# FPGA.net
KiCad netlist of a schematic drawn in Altium Designer
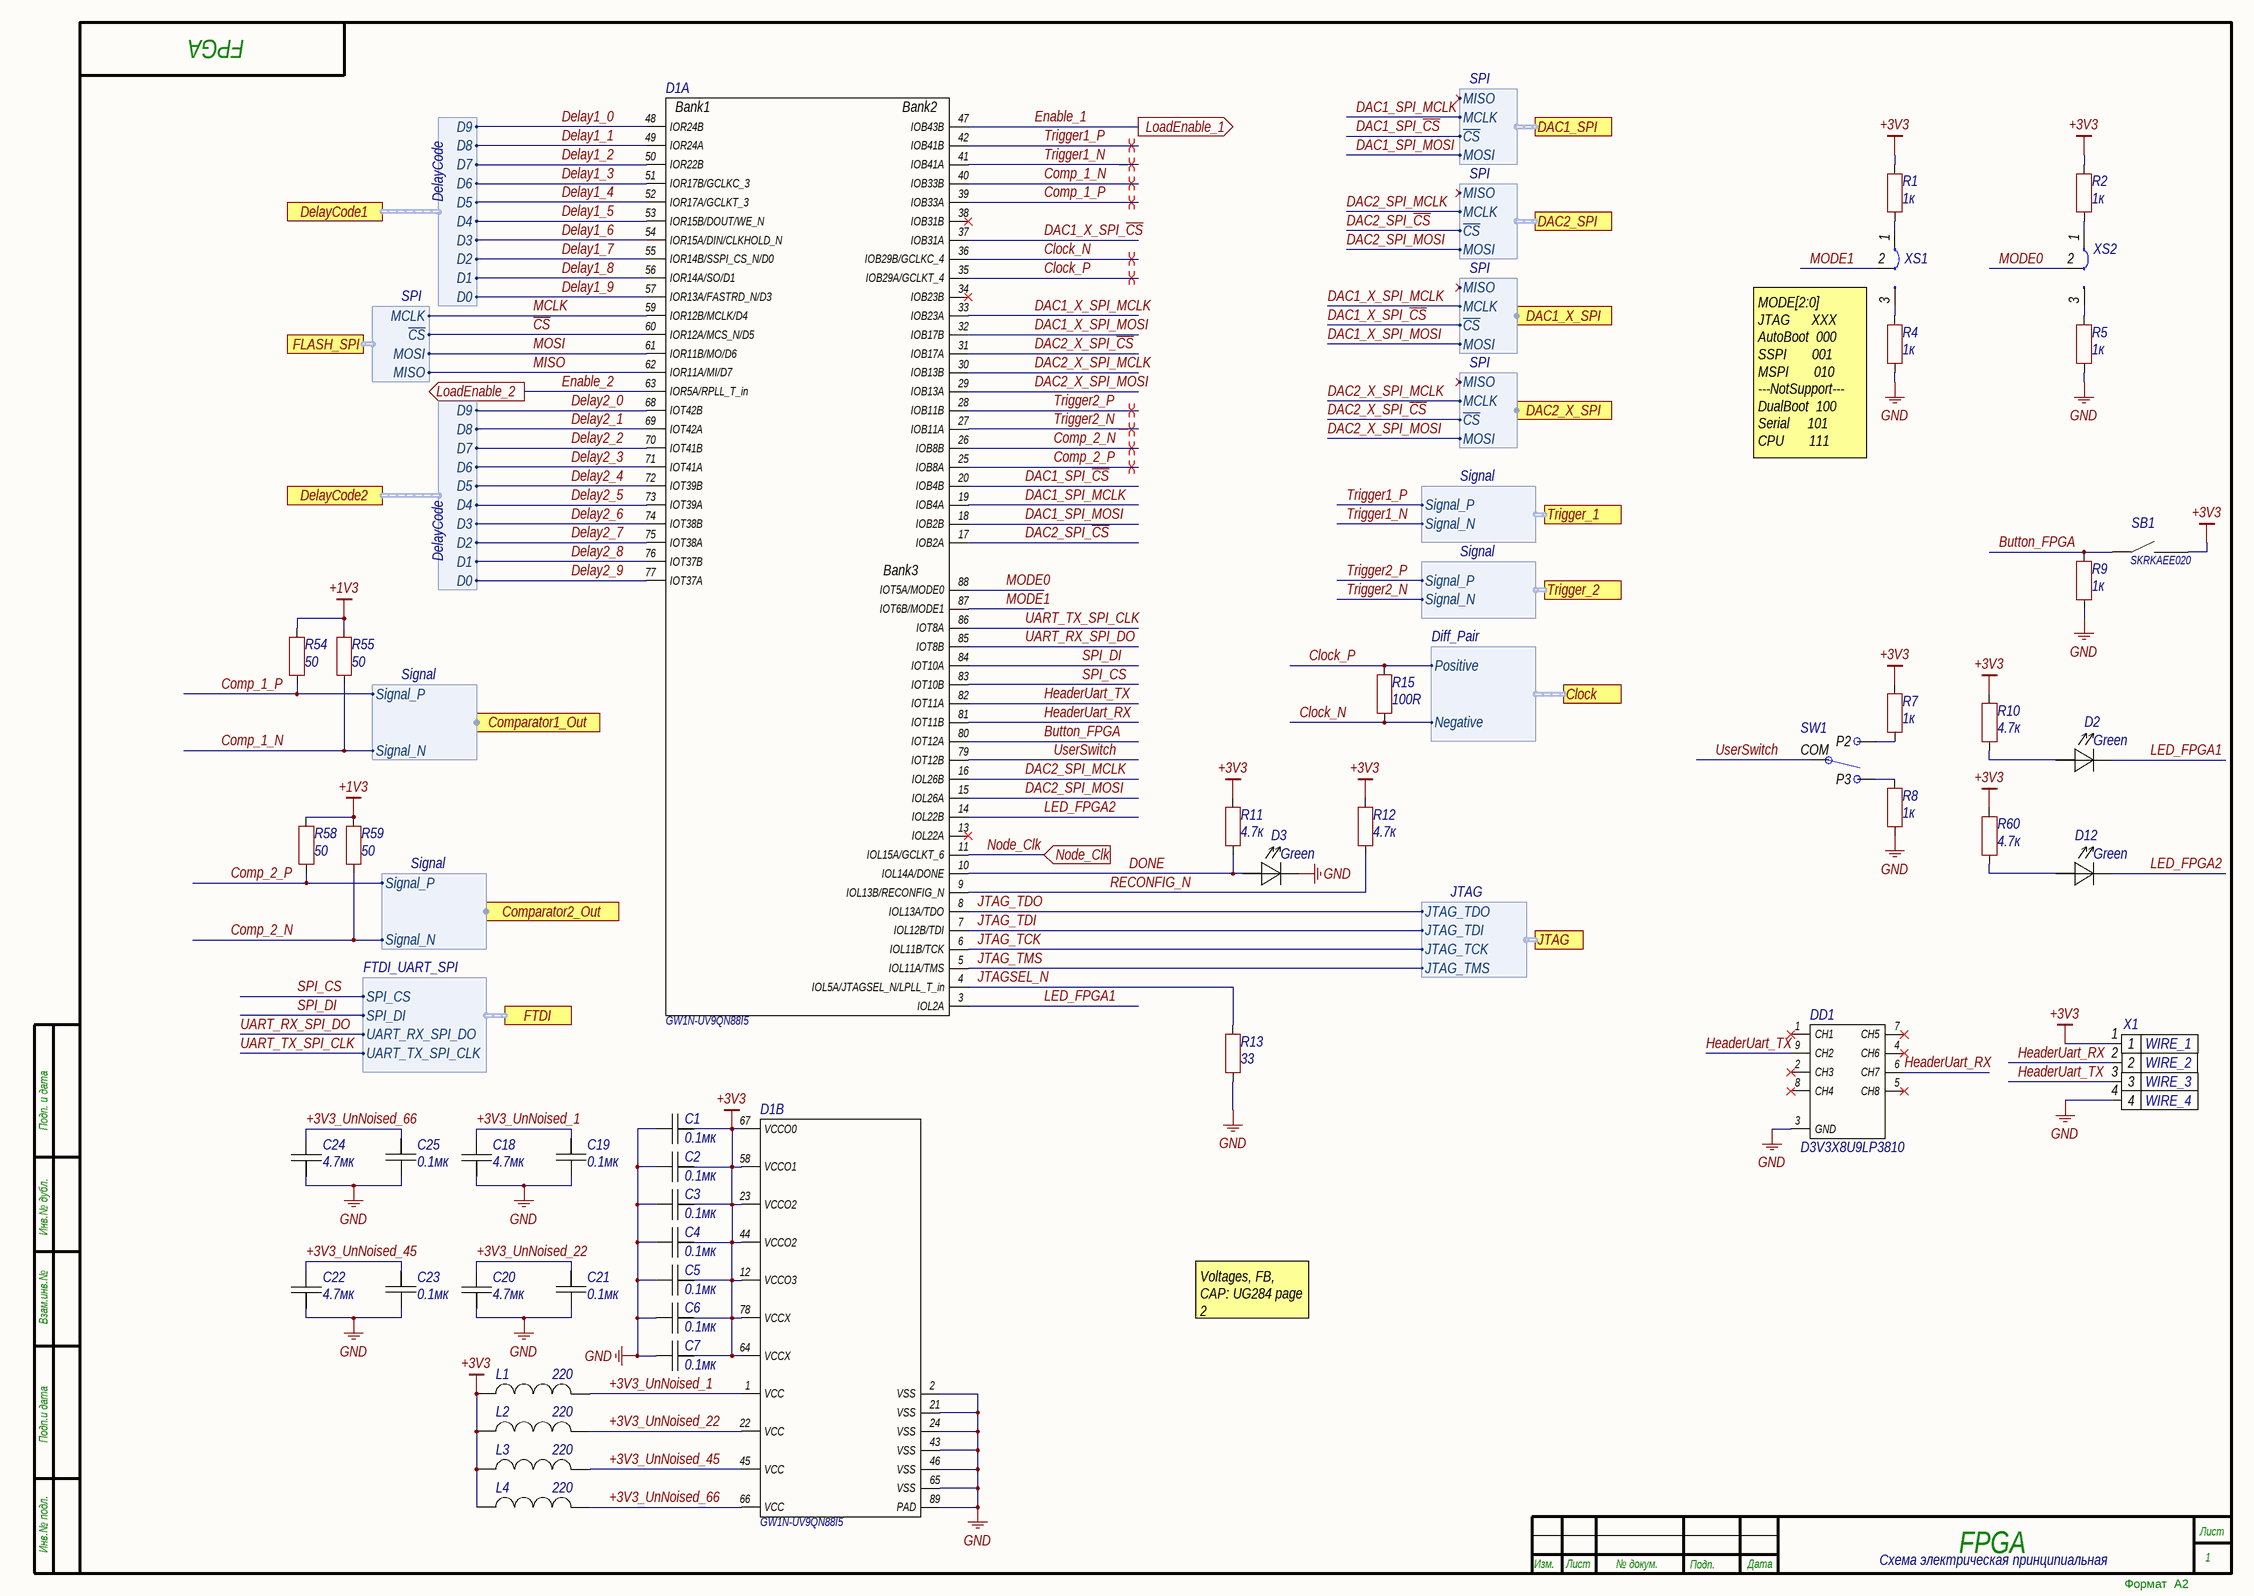
[diagram p0: FPGA.SchDoc]

(export (version "E")
  (design (tool "Eeschema 10.0.6"))
  (components
    (comp (ref "C1")
      (value "0.1мк")
      (footprint "CAP0402")
      (fields
        (field (name "MANUFACTURER") "Samsung Electro-Mechanics")
        (field (name "MPN") "CL05B104KB54PNC")
        (field (name "TOLERANCE") "10%")
      )
      (libsource (lib "Library") (part "CAPC"))
    )
    (comp (ref "C2")
      (value "0.1мк")
      (footprint "CAP0402")
      (fields
        (field (name "MANUFACTURER") "Samsung Electro-Mechanics")
        (field (name "MPN") "CL05B104KB54PNC")
        (field (name "TOLERANCE") "10%")
      )
      (libsource (lib "Library") (part "CAPC"))
    )
    (comp (ref "C3")
      (value "0.1мк")
      (footprint "CAP0402")
      (fields
        (field (name "MANUFACTURER") "Samsung Electro-Mechanics")
        (field (name "MPN") "CL05B104KB54PNC")
        (field (name "TOLERANCE") "10%")
      )
      (libsource (lib "Library") (part "CAPC"))
    )
    (comp (ref "C4")
      (value "0.1мк")
      (footprint "CAP0402")
      (fields
        (field (name "MANUFACTURER") "Samsung Electro-Mechanics")
        (field (name "MPN") "CL05B104KB54PNC")
        (field (name "TOLERANCE") "10%")
      )
      (libsource (lib "Library") (part "CAPC"))
    )
    (comp (ref "C5")
      (value "0.1мк")
      (footprint "CAP0402")
      (fields
        (field (name "MANUFACTURER") "Samsung Electro-Mechanics")
        (field (name "MPN") "CL05B104KB54PNC")
        (field (name "TOLERANCE") "10%")
      )
      (libsource (lib "Library") (part "CAPC"))
    )
    (comp (ref "C6")
      (value "0.1мк")
      (footprint "CAP0402")
      (fields
        (field (name "MANUFACTURER") "Samsung Electro-Mechanics")
        (field (name "MPN") "CL05B104KB54PNC")
        (field (name "TOLERANCE") "10%")
      )
      (libsource (lib "Library") (part "CAPC"))
    )
    (comp (ref "C7")
      (value "0.1мк")
      (footprint "CAP0402")
      (fields
        (field (name "MANUFACTURER") "Samsung Electro-Mechanics")
        (field (name "MPN") "CL05B104KB54PNC")
        (field (name "TOLERANCE") "10%")
      )
      (libsource (lib "Library") (part "CAPC"))
    )
    (comp (ref "C18")
      (value "4.7мк")
      (footprint "CAP0402")
      (fields
        (field (name "MANUFACTURER") "Samsung Electro-Mechanics")
        (field (name "MPN") "CL05A475MP5NRNC")
        (field (name "TOLERANCE") "20%")
      )
      (libsource (lib "Library") (part "CAPC"))
    )
    (comp (ref "C19")
      (value "0.1мк")
      (footprint "CAP0402")
      (fields
        (field (name "MANUFACTURER") "Samsung Electro-Mechanics")
        (field (name "MPN") "CL05B104KB54PNC")
        (field (name "TOLERANCE") "10%")
      )
      (libsource (lib "Library") (part "CAPC"))
    )
    (comp (ref "C20")
      (value "4.7мк")
      (footprint "CAP0402")
      (fields
        (field (name "MANUFACTURER") "Samsung Electro-Mechanics")
        (field (name "MPN") "CL05A475MP5NRNC")
        (field (name "TOLERANCE") "20%")
      )
      (libsource (lib "Library") (part "CAPC"))
    )
    (comp (ref "C21")
      (value "0.1мк")
      (footprint "CAP0402")
      (fields
        (field (name "MANUFACTURER") "Samsung Electro-Mechanics")
        (field (name "MPN") "CL05B104KB54PNC")
        (field (name "TOLERANCE") "10%")
      )
      (libsource (lib "Library") (part "CAPC"))
    )
    (comp (ref "C22")
      (value "4.7мк")
      (footprint "CAP0402")
      (fields
        (field (name "MANUFACTURER") "Samsung Electro-Mechanics")
        (field (name "MPN") "CL05A475MP5NRNC")
        (field (name "TOLERANCE") "20%")
      )
      (libsource (lib "Library") (part "CAPC"))
    )
    (comp (ref "C23")
      (value "0.1мк")
      (footprint "CAP0402")
      (fields
        (field (name "MANUFACTURER") "Samsung Electro-Mechanics")
        (field (name "MPN") "CL05B104KB54PNC")
        (field (name "TOLERANCE") "10%")
      )
      (libsource (lib "Library") (part "CAPC"))
    )
    (comp (ref "C24")
      (value "4.7мк")
      (footprint "CAP0402")
      (fields
        (field (name "MANUFACTURER") "Samsung Electro-Mechanics")
        (field (name "MPN") "CL05A475MP5NRNC")
        (field (name "TOLERANCE") "20%")
      )
      (libsource (lib "Library") (part "CAPC"))
    )
    (comp (ref "C25")
      (value "0.1мк")
      (footprint "CAP0402")
      (fields
        (field (name "MANUFACTURER") "Samsung Electro-Mechanics")
        (field (name "MPN") "CL05B104KB54PNC")
        (field (name "TOLERANCE") "10%")
      )
      (libsource (lib "Library") (part "CAPC"))
    )
    (comp (ref "D1")
      (value "~")
      (footprint "QFN88_0.4pitch")
      (fields
        (field (name "MPN") "GW1N-UV9QN88I5")
        (field (name "PART NUMBER") "GW1N-UV9QN88I5")
        (field (name "MANUFACTURER") "GoWin")
      )
      (libsource (lib "Library") (part "D_GW1N-UV9QN88I5"))
    )
    (comp (ref "D2")
      (value "Green")
      (footprint "LED603")
      (fields
        (field (name "MANUFACTURER") "Everlight Elec")
        (field (name "MPN") "19-217/GHC-YR1S2/3T")
        (field (name "PART NUMBER") "LEDC")
      )
      (libsource (lib "Library") (part "LEDC"))
    )
    (comp (ref "D3")
      (value "Green")
      (footprint "LED603")
      (fields
        (field (name "MANUFACTURER") "Everlight Elec")
        (field (name "MPN") "19-217/GHC-YR1S2/3T")
        (field (name "PART NUMBER") "LEDC")
      )
      (libsource (lib "Library") (part "LEDC"))
    )
    (comp (ref "D12")
      (value "Green")
      (footprint "LED603")
      (fields (field (name "PART NUMBER") "LEDC"))
      (libsource (lib "Library") (part "LEDC"))
    )
    (comp (ref "DD1")
      (value "TVS Diode at JTAG")
      (footprint "U-DFN3810-9")
      (fields
        (field (name "MPN") "D3V3X8U9LP3810")
        (field (name "PART NUMBER") "D3V3X8U9LP3810")
        (field (name "MANUFACTURER") "DiodesInc")
      )
      (libsource (lib "Library") (part "DD_D3V3X8U9LP3810"))
    )
    (comp (ref "L1")
      (value "220")
      (footprint "CAPC0603N")
      (fields
        (field (name "MANUFACTURER") "Murata Electronics")
        (field (name "MPN") "BLM18KG221SN1D")
        (field (name "TOLERANCE") "25%")
      )
      (libsource (lib "Library") (part "Inductor"))
    )
    (comp (ref "L2")
      (value "220")
      (footprint "CAPC0603N")
      (fields
        (field (name "MANUFACTURER") "Murata Electronics")
        (field (name "MPN") "BLM18KG221SN1D")
        (field (name "TOLERANCE") "25%")
      )
      (libsource (lib "Library") (part "Inductor"))
    )
    (comp (ref "L3")
      (value "220")
      (footprint "CAPC0603N")
      (fields
        (field (name "MANUFACTURER") "Murata Electronics")
        (field (name "MPN") "BLM18KG221SN1D")
        (field (name "TOLERANCE") "25%")
      )
      (libsource (lib "Library") (part "Inductor"))
    )
    (comp (ref "L4")
      (value "220")
      (footprint "CAPC0603N")
      (fields
        (field (name "MANUFACTURER") "Murata Electronics")
        (field (name "MPN") "BLM18KG221SN1D")
        (field (name "TOLERANCE") "25%")
      )
      (libsource (lib "Library") (part "Inductor"))
    )
    (comp (ref "R1")
      (value "1к")
      (footprint "RESC0402(1005)_M")
      (fields
        (field (name "MANUFACTURER") "UNI-ROYAL")
        (field (name "MPN") "0402WGF1001TCE")
        (field (name "POWER") "1/16W")
      )
      (libsource (lib "Library") (part "RES"))
    )
    (comp (ref "R2")
      (value "1к")
      (footprint "RESC0402(1005)_M")
      (fields
        (field (name "MANUFACTURER") "UNI-ROYAL")
        (field (name "MPN") "0402WGF1001TCE")
        (field (name "POWER") "1/16W")
      )
      (libsource (lib "Library") (part "RES"))
    )
    (comp (ref "R4")
      (value "1к")
      (footprint "RESC0402(1005)_M")
      (fields
        (field (name "MANUFACTURER") "UNI-ROYAL")
        (field (name "MPN") "0402WGF1001TCE")
        (field (name "POWER") "1/16W")
      )
      (libsource (lib "Library") (part "RES"))
    )
    (comp (ref "R5")
      (value "1к")
      (footprint "RESC0402(1005)_M")
      (fields
        (field (name "MANUFACTURER") "UNI-ROYAL")
        (field (name "MPN") "0402WGF1001TCE")
        (field (name "POWER") "1/16W")
      )
      (libsource (lib "Library") (part "RES"))
    )
    (comp (ref "R7")
      (value "1к")
      (footprint "RESC0402(1005)_M")
      (fields
        (field (name "MANUFACTURER") "UNI-ROYAL")
        (field (name "MPN") "0402WGF1001TCE")
        (field (name "POWER") "1/16W")
      )
      (libsource (lib "Library") (part "RES"))
    )
    (comp (ref "R8")
      (value "1к")
      (footprint "RESC0402(1005)_M")
      (fields
        (field (name "MANUFACTURER") "UNI-ROYAL")
        (field (name "MPN") "0402WGF1001TCE")
        (field (name "POWER") "1/16W")
      )
      (libsource (lib "Library") (part "RES"))
    )
    (comp (ref "R9")
      (value "1к")
      (footprint "RESC0402(1005)_M")
      (fields (field (name "PART NUMBER") "RES0402") (field (name "Comment") "1к "))
      (libsource (lib "Library") (part "RES"))
    )
    (comp (ref "R10")
      (value "4.7к")
      (footprint "RESC0402(1005)_M")
      (fields
        (field (name "MANUFACTURER") "UNI-ROYAL")
        (field (name "MPN") "0402WGF4701TCE")
        (field (name "PART NUMBER") "RES0402")
      )
      (libsource (lib "Library") (part "RES"))
    )
    (comp (ref "R11")
      (value "4.7к")
      (footprint "RESC0402(1005)_M")
      (fields
        (field (name "MANUFACTURER") "UNI-ROYAL")
        (field (name "MPN") "0402WGF4701TCE")
        (field (name "PART NUMBER") "RES0402")
      )
      (libsource (lib "Library") (part "RES"))
    )
    (comp (ref "R12")
      (value "4.7к")
      (footprint "RESC0402(1005)_M")
      (fields
        (field (name "MANUFACTURER") "UNI-ROYAL")
        (field (name "MPN") "0402WGF4701TCE")
        (field (name "PART NUMBER") "RES0402")
      )
      (libsource (lib "Library") (part "RES"))
    )
    (comp (ref "R13")
      (value "33")
      (footprint "RESC0402(1005)_M")
      (fields
        (field (name "MANUFACTURER") "UNI-ROYAL")
        (field (name "MPN") "0402WGF330JTCE")
        (field (name "POWER") "1/16W")
      )
      (libsource (lib "Library") (part "RES"))
    )
    (comp (ref "R15")
      (value "100R")
      (footprint "RESC0402(1005)_M")
      (fields (field (name "PART NUMBER") "RES0402") (field (name "Comment") "100R "))
      (libsource (lib "Library") (part "RES"))
    )
    (comp (ref "R54")
      (value "50")
      (footprint "RESC0402(1005)_M")
      (fields (field (name "PART NUMBER") "RES0402") (field (name "Comment") "50 "))
      (libsource (lib "Library") (part "RES"))
    )
    (comp (ref "R55")
      (value "50")
      (footprint "RESC0402(1005)_M")
      (fields (field (name "PART NUMBER") "RES0402") (field (name "Comment") "50 "))
      (libsource (lib "Library") (part "RES"))
    )
    (comp (ref "R58")
      (value "50")
      (footprint "RESC0402(1005)_M")
      (fields (field (name "PART NUMBER") "RES0402") (field (name "Comment") "50 "))
      (libsource (lib "Library") (part "RES"))
    )
    (comp (ref "R59")
      (value "50")
      (footprint "RESC0402(1005)_M")
      (fields (field (name "PART NUMBER") "RES0402") (field (name "Comment") "50 "))
      (libsource (lib "Library") (part "RES"))
    )
    (comp (ref "R60")
      (value "4.7к")
      (footprint "RESC0402(1005)_M")
      (fields (field (name "PART NUMBER") "RES0402") (field (name "Comment") "4.7к "))
      (libsource (lib "Library") (part "RES"))
    )
    (comp (ref "SB1")
      (value "DTSM-3")
      (footprint "SW_SKRKAEE020")
      (fields (field (name "MPN") "SKRKAEE020") (field (name "PART NUMBER") "SKRKAEE020"))
      (libsource (lib "Library") (part "DTSM-3"))
    )
    (comp (ref "SW1")
      (value "Slide Switch")
      (footprint "KLS7-SS03-12D02-EG-3.0")
      (description "Toggle Switch SPDT Through Hole, Right Angle")
      (fields (field (name "MPN") "KLS7-SS03-12D02-EG-3.0") (field (name "MANUFACTURER") "KLS Electronic"))
      (libsource (lib "Library") (part "Single-pole toggle switch"))
    )
    (comp (ref "X1")
      (value "PLS4")
      (footprint "PLS4")
      (fields
        (field (name "WIRE1") "WIRE_1")
        (field (name "WIRE2") "WIRE_2")
        (field (name "WIRE3") "WIRE_3")
        (field (name "WIRE4") "WIRE_4")
      )
      (libsource (lib "Library") (part "PLS4"))
    )
    (comp (ref "XS1")
      (value "PLS3")
      (footprint "PLS3")
      (fields (field (name "PART NUMBER") "Jumper_PLS3"))
      (libsource (lib "Library") (part "Jumper_3_pin"))
    )
    (comp (ref "XS2")
      (value "PLS3")
      (footprint "PLS3")
      (fields (field (name "PART NUMBER") "Jumper_PLS3"))
      (libsource (lib "Library") (part "Jumper_3_pin"))
    )
  )
  (nets
    (net (code "7") (name "+1V3") (class "Default")
      (node (ref "R54") (pin "2") (pinfunction "2_2") (pintype "passive"))
      (node (ref "R55") (pin "2") (pinfunction "2_2") (pintype "passive"))
      (node (ref "R58") (pin "2") (pinfunction "2_2") (pintype "passive"))
      (node (ref "R59") (pin "2") (pinfunction "2_2") (pintype "passive"))
    )
    (net (code "8") (name "+3V3") (class "Default")
      (node (ref "C1") (pin "1") (pinfunction "1_1") (pintype "passive"))
      (node (ref "C2") (pin "1") (pinfunction "1_1") (pintype "passive"))
      (node (ref "C3") (pin "1") (pinfunction "1_1") (pintype "passive"))
      (node (ref "C4") (pin "1") (pinfunction "1_1") (pintype "passive"))
      (node (ref "C5") (pin "1") (pinfunction "1_1") (pintype "passive"))
      (node (ref "C6") (pin "1") (pinfunction "1_1") (pintype "passive"))
      (node (ref "C7") (pin "1") (pinfunction "1_1") (pintype "passive"))
      (node (ref "D1") (pin "12") (pinfunction "VCCO3_12") (pintype "passive"))
      (node (ref "D1") (pin "23") (pinfunction "VCCO2_23") (pintype "passive"))
      (node (ref "D1") (pin "44") (pinfunction "VCCO2_44") (pintype "passive"))
      (node (ref "D1") (pin "58") (pinfunction "VCCO1_58") (pintype "passive"))
      (node (ref "D1") (pin "64") (pinfunction "VCCX_64") (pintype "passive"))
      (node (ref "D1") (pin "67") (pinfunction "VCCO0_67") (pintype "passive"))
      (node (ref "D1") (pin "78") (pinfunction "VCCX_78") (pintype "passive"))
      (node (ref "L1") (pin "1") (pinfunction "1_1") (pintype "passive"))
      (node (ref "L2") (pin "1") (pinfunction "1_1") (pintype "passive"))
      (node (ref "L3") (pin "1") (pinfunction "1_1") (pintype "passive"))
      (node (ref "L4") (pin "1") (pinfunction "1_1") (pintype "passive"))
      (node (ref "R1") (pin "2") (pinfunction "2_2") (pintype "passive"))
      (node (ref "R10") (pin "2") (pinfunction "2_2") (pintype "passive"))
      (node (ref "R11") (pin "2") (pinfunction "2_2") (pintype "passive"))
      (node (ref "R12") (pin "2") (pinfunction "2_2") (pintype "passive"))
      (node (ref "R2") (pin "2") (pinfunction "2_2") (pintype "passive"))
      (node (ref "R60") (pin "2") (pinfunction "2_2") (pintype "passive"))
      (node (ref "R7") (pin "2") (pinfunction "2_2") (pintype "passive"))
      (node (ref "SB1") (pin "1") (pinfunction "1_1") (pintype "passive"))
      (node (ref "X1") (pin "1") (pinfunction "1_1") (pintype "passive"))
    )
    (net (code "9") (name "/+3V3_UnNoised_1") (class "Default")
      (node (ref "C18") (pin "2") (pinfunction "2_2") (pintype "passive"))
      (node (ref "C19") (pin "1") (pinfunction "1_1") (pintype "passive"))
      (node (ref "D1") (pin "1") (pinfunction "VCC_1") (pintype "passive"))
      (node (ref "L1") (pin "2") (pinfunction "2_2") (pintype "passive"))
    )
    (net (code "10") (name "/+3V3_UnNoised_22") (class "Default")
      (node (ref "C20") (pin "2") (pinfunction "2_2") (pintype "passive"))
      (node (ref "C21") (pin "1") (pinfunction "1_1") (pintype "passive"))
      (node (ref "D1") (pin "22") (pinfunction "VCC_22") (pintype "passive"))
      (node (ref "L2") (pin "2") (pinfunction "2_2") (pintype "passive"))
    )
    (net (code "11") (name "/+3V3_UnNoised_45") (class "Default")
      (node (ref "C22") (pin "2") (pinfunction "2_2") (pintype "passive"))
      (node (ref "C23") (pin "1") (pinfunction "1_1") (pintype "passive"))
      (node (ref "D1") (pin "45") (pinfunction "VCC_45") (pintype "passive"))
      (node (ref "L3") (pin "2") (pinfunction "2_2") (pintype "passive"))
    )
    (net (code "12") (name "/+3V3_UnNoised_66") (class "Default")
      (node (ref "C24") (pin "2") (pinfunction "2_2") (pintype "passive"))
      (node (ref "C25") (pin "1") (pinfunction "1_1") (pintype "passive"))
      (node (ref "D1") (pin "66") (pinfunction "VCC_66") (pintype "passive"))
      (node (ref "L4") (pin "2") (pinfunction "2_2") (pintype "passive"))
    )
    (net (code "13") (name "/Button_FPGA") (class "Default")
      (node (ref "D1") (pin "80") (pinfunction "IOT12A_80") (pintype "passive"))
      (node (ref "R9") (pin "2") (pinfunction "2_2") (pintype "passive"))
      (node (ref "SB1") (pin "2") (pinfunction "2_2") (pintype "passive"))
    )
    (net (code "14") (name "/Clock_N") (class "Default")
      (node (ref "D1") (pin "36") (pinfunction "IOB29B/GCLKC_4_36") (pintype "passive"))
      (node (ref "R15") (pin "1") (pinfunction "1_1") (pintype "passive"))
    )
    (net (code "15") (name "/Clock_P") (class "Default")
      (node (ref "D1") (pin "35") (pinfunction "IOB29A/GCLKT_4_35") (pintype "passive"))
      (node (ref "R15") (pin "2") (pinfunction "2_2") (pintype "passive"))
    )
    (net (code "16") (name "/Comp_1_N") (class "Default")
      (node (ref "D1") (pin "40") (pinfunction "IOB33B_40") (pintype "passive"))
      (node (ref "R55") (pin "1") (pinfunction "1_1") (pintype "passive"))
    )
    (net (code "17") (name "/Comp_1_P") (class "Default")
      (node (ref "D1") (pin "39") (pinfunction "IOB33A_39") (pintype "passive"))
      (node (ref "R54") (pin "1") (pinfunction "1_1") (pintype "passive"))
    )
    (net (code "18") (name "/Comp_2_N") (class "Default")
      (node (ref "D1") (pin "26") (pinfunction "IOB8B_26") (pintype "passive"))
      (node (ref "R59") (pin "1") (pinfunction "1_1") (pintype "passive"))
    )
    (net (code "19") (name "/Comp_2_P") (class "Default")
      (node (ref "D1") (pin "25") (pinfunction "IOB8A_25") (pintype "passive"))
      (node (ref "R58") (pin "1") (pinfunction "1_1") (pintype "passive"))
    )
    (net (code "20") (name "/DAC1_SPI_MCLK") (class "Default")
      (node (ref "D1") (pin "19") (pinfunction "IOB4A_19") (pintype "passive"))
    )
    (net (code "21") (name "/DAC1_SPI_MOSI") (class "Default")
      (node (ref "D1") (pin "18") (pinfunction "IOB2B_18") (pintype "passive"))
    )
    (net (code "22") (name "/DAC1_SPI_~{CS}") (class "Default")
      (node (ref "D1") (pin "20") (pinfunction "IOB4B_20") (pintype "passive"))
    )
    (net (code "23") (name "/DAC1_X_SPI_MCLK") (class "Default")
      (node (ref "D1") (pin "33") (pinfunction "IOB23A_33") (pintype "passive"))
    )
    (net (code "24") (name "/DAC1_X_SPI_MOSI") (class "Default")
      (node (ref "D1") (pin "32") (pinfunction "IOB17B_32") (pintype "passive"))
    )
    (net (code "25") (name "/DAC1_X_SPI_~{CS}") (class "Default")
      (node (ref "D1") (pin "37") (pinfunction "IOB31A_37") (pintype "passive"))
    )
    (net (code "26") (name "/DAC2_SPI_MCLK") (class "Default")
      (node (ref "D1") (pin "16") (pinfunction "IOL26B_16") (pintype "passive"))
    )
    (net (code "27") (name "/DAC2_SPI_MOSI") (class "Default")
      (node (ref "D1") (pin "15") (pinfunction "IOL26A_15") (pintype "passive"))
    )
    (net (code "28") (name "/DAC2_SPI_~{CS}") (class "Default")
      (node (ref "D1") (pin "17") (pinfunction "IOB2A_17") (pintype "passive"))
    )
    (net (code "29") (name "/DAC2_X_SPI_MCLK") (class "Default")
      (node (ref "D1") (pin "30") (pinfunction "IOB13B_30") (pintype "passive"))
    )
    (net (code "30") (name "/DAC2_X_SPI_MOSI") (class "Default")
      (node (ref "D1") (pin "29") (pinfunction "IOB13A_29") (pintype "passive"))
    )
    (net (code "31") (name "/DAC2_X_SPI_~{CS}") (class "Default")
      (node (ref "D1") (pin "31") (pinfunction "IOB17A_31") (pintype "passive"))
    )
    (net (code "32") (name "/DONE") (class "Default")
      (node (ref "D1") (pin "10") (pinfunction "IOL14A/DONE_10") (pintype "passive"))
      (node (ref "D3") (pin "2") (pinfunction "K_2") (pintype "passive"))
      (node (ref "R11") (pin "1") (pinfunction "1_1") (pintype "passive"))
    )
    (net (code "33") (name "/Delay1_0") (class "Default")
      (node (ref "D1") (pin "48") (pinfunction "IOR24B_48") (pintype "passive"))
    )
    (net (code "34") (name "/Delay1_1") (class "Default")
      (node (ref "D1") (pin "49") (pinfunction "IOR24A_49") (pintype "passive"))
    )
    (net (code "35") (name "/Delay1_2") (class "Default")
      (node (ref "D1") (pin "50") (pinfunction "IOR22B_50") (pintype "passive"))
    )
    (net (code "36") (name "/Delay1_3") (class "Default")
      (node (ref "D1") (pin "51") (pinfunction "IOR17B/GCLKC_3_51") (pintype "passive"))
    )
    (net (code "37") (name "/Delay1_4") (class "Default")
      (node (ref "D1") (pin "52") (pinfunction "IOR17A/GCLKT_3_52") (pintype "passive"))
    )
    (net (code "38") (name "/Delay1_5") (class "Default")
      (node (ref "D1") (pin "53") (pinfunction "IOR15B/DOUT/WE_N_53") (pintype "passive"))
    )
    (net (code "39") (name "/Delay1_6") (class "Default")
      (node (ref "D1") (pin "54") (pinfunction "IOR15A/DIN/CLKHOLD_N_54") (pintype "passive"))
    )
    (net (code "40") (name "/Delay1_7") (class "Default")
      (node (ref "D1") (pin "55") (pinfunction "IOR14B/SSPI_CS_N/D0_55") (pintype "passive"))
    )
    (net (code "41") (name "/Delay1_8") (class "Default")
      (node (ref "D1") (pin "56") (pinfunction "IOR14A/SO/D1_56") (pintype "passive"))
    )
    (net (code "42") (name "/Delay1_9") (class "Default")
      (node (ref "D1") (pin "57") (pinfunction "IOR13A/FASTRD_N/D3_57") (pintype "passive"))
    )
    (net (code "43") (name "/Delay2_0") (class "Default")
      (node (ref "D1") (pin "68") (pinfunction "IOT42B_68") (pintype "passive"))
    )
    (net (code "44") (name "/Delay2_1") (class "Default")
      (node (ref "D1") (pin "69") (pinfunction "IOT42A_69") (pintype "passive"))
    )
    (net (code "45") (name "/Delay2_2") (class "Default")
      (node (ref "D1") (pin "70") (pinfunction "IOT41B_70") (pintype "passive"))
    )
    (net (code "46") (name "/Delay2_3") (class "Default")
      (node (ref "D1") (pin "71") (pinfunction "IOT41A_71") (pintype "passive"))
    )
    (net (code "47") (name "/Delay2_4") (class "Default")
      (node (ref "D1") (pin "72") (pinfunction "IOT39B_72") (pintype "passive"))
    )
    (net (code "48") (name "/Delay2_5") (class "Default")
      (node (ref "D1") (pin "73") (pinfunction "IOT39A_73") (pintype "passive"))
    )
    (net (code "49") (name "/Delay2_6") (class "Default")
      (node (ref "D1") (pin "74") (pinfunction "IOT38B_74") (pintype "passive"))
    )
    (net (code "50") (name "/Delay2_7") (class "Default")
      (node (ref "D1") (pin "75") (pinfunction "IOT38A_75") (pintype "passive"))
    )
    (net (code "51") (name "/Delay2_8") (class "Default")
      (node (ref "D1") (pin "76") (pinfunction "IOT37B_76") (pintype "passive"))
    )
    (net (code "52") (name "/Delay2_9") (class "Default")
      (node (ref "D1") (pin "77") (pinfunction "IOT37A_77") (pintype "passive"))
    )
    (net (code "53") (name "/Enable_1") (class "Default")
      (node (ref "D1") (pin "47") (pinfunction "IOB43B_47") (pintype "passive"))
    )
    (net (code "54") (name "/Enable_2") (class "Default")
      (node (ref "D1") (pin "63") (pinfunction "IOR5A/RPLL_T_in_63") (pintype "passive"))
    )
    (net (code "55") (name "/HeaderUart_RX") (class "Default")
      (node (ref "D1") (pin "81") (pinfunction "IOT11B_81") (pintype "passive"))
      (node (ref "DD1") (pin "6") (pinfunction "CH7_6") (pintype "passive"))
      (node (ref "X1") (pin "2") (pinfunction "2_2") (pintype "passive"))
    )
    (net (code "56") (name "/HeaderUart_TX") (class "Default")
      (node (ref "D1") (pin "82") (pinfunction "IOT11A_82") (pintype "passive"))
      (node (ref "DD1") (pin "9") (pinfunction "CH2_9") (pintype "passive"))
      (node (ref "X1") (pin "3") (pinfunction "3_3") (pintype "passive"))
    )
    (net (code "57") (name "/JTAGSEL_N") (class "Default")
      (node (ref "D1") (pin "4") (pinfunction "IOL5A/JTAGSEL_N/LPLL_T_in_4") (pintype "passive"))
      (node (ref "R13") (pin "2") (pinfunction "2_2") (pintype "passive"))
    )
    (net (code "58") (name "/JTAG_TCK") (class "Default")
      (node (ref "D1") (pin "6") (pinfunction "IOL11B/TCK_6") (pintype "passive"))
    )
    (net (code "59") (name "/JTAG_TDI") (class "Default")
      (node (ref "D1") (pin "7") (pinfunction "IOL12B/TDI_7") (pintype "passive"))
    )
    (net (code "60") (name "/JTAG_TDO") (class "Default")
      (node (ref "D1") (pin "8") (pinfunction "IOL13A/TDO_8") (pintype "passive"))
    )
    (net (code "61") (name "/JTAG_TMS") (class "Default")
      (node (ref "D1") (pin "5") (pinfunction "IOL11A/TMS_5") (pintype "passive"))
    )
    (net (code "62") (name "/LED_FPGA1") (class "Default")
      (node (ref "D1") (pin "3") (pinfunction "IOL2A_3") (pintype "passive"))
      (node (ref "D2") (pin "1") (pinfunction "A_1") (pintype "passive"))
    )
    (net (code "63") (name "/LED_FPGA2") (class "Default")
      (node (ref "D1") (pin "14") (pinfunction "IOL22B_14") (pintype "passive"))
      (node (ref "D12") (pin "1") (pinfunction "A_1") (pintype "passive"))
    )
    (net (code "64") (name "/MCLK") (class "Default")
      (node (ref "D1") (pin "59") (pinfunction "IOR12B/MCLK/D4_59") (pintype "passive"))
    )
    (net (code "65") (name "/MISO") (class "Default")
      (node (ref "D1") (pin "62") (pinfunction "IOR11A/MI/D7_62") (pintype "passive"))
    )
    (net (code "66") (name "/MODE0") (class "Default")
      (node (ref "D1") (pin "88") (pinfunction "IOT5A/MODE0_88") (pintype "passive"))
      (node (ref "XS2") (pin "2") (pinfunction "2_2") (pintype "passive"))
    )
    (net (code "67") (name "/MODE1") (class "Default")
      (node (ref "D1") (pin "87") (pinfunction "IOT6B/MODE1_87") (pintype "passive"))
      (node (ref "XS1") (pin "2") (pinfunction "2_2") (pintype "passive"))
    )
    (net (code "68") (name "/MOSI") (class "Default")
      (node (ref "D1") (pin "61") (pinfunction "IOR11B/MO/D6_61") (pintype "passive"))
    )
    (net (code "69") (name "/Node_Clk") (class "Default")
      (node (ref "D1") (pin "11") (pinfunction "IOL15A/GCLKT_6_11") (pintype "passive"))
    )
    (net (code "70") (name "/RECONFIG_N") (class "Default")
      (node (ref "D1") (pin "9") (pinfunction "IOL13B/RECONFIG_N_9") (pintype "passive"))
      (node (ref "R12") (pin "1") (pinfunction "1_1") (pintype "passive"))
    )
    (net (code "71") (name "/SPI_CS") (class "Default")
      (node (ref "D1") (pin "83") (pinfunction "IOT10B_83") (pintype "passive"))
    )
    (net (code "72") (name "/SPI_DI") (class "Default")
      (node (ref "D1") (pin "84") (pinfunction "IOT10A_84") (pintype "passive"))
    )
    (net (code "73") (name "/Trigger1_N") (class "Default")
      (node (ref "D1") (pin "41") (pinfunction "IOB41A_41") (pintype "passive"))
    )
    (net (code "74") (name "/Trigger1_P") (class "Default")
      (node (ref "D1") (pin "42") (pinfunction "IOB41B_42") (pintype "passive"))
    )
    (net (code "75") (name "/Trigger2_N") (class "Default")
      (node (ref "D1") (pin "27") (pinfunction "IOB11A_27") (pintype "passive"))
    )
    (net (code "76") (name "/Trigger2_P") (class "Default")
      (node (ref "D1") (pin "28") (pinfunction "IOB11B_28") (pintype "passive"))
    )
    (net (code "77") (name "/UART_RX_SPI_DO") (class "Default")
      (node (ref "D1") (pin "85") (pinfunction "IOT8B_85") (pintype "passive"))
    )
    (net (code "78") (name "/UART_TX_SPI_CLK") (class "Default")
      (node (ref "D1") (pin "86") (pinfunction "IOT8A_86") (pintype "passive"))
    )
    (net (code "79") (name "/UserSwitch") (class "Default")
      (node (ref "D1") (pin "79") (pinfunction "IOT12B_79") (pintype "passive"))
      (node (ref "SW1") (pin "2") (pinfunction "COM_2") (pintype "passive"))
    )
    (net (code "86") (name "/~{CS}") (class "Default")
      (node (ref "D1") (pin "60") (pinfunction "IOR12A/MCS_N/D5_60") (pintype "passive"))
    )
    (net (code "87") (name "GND") (class "Default")
      (node (ref "C1") (pin "2") (pinfunction "2_2") (pintype "passive"))
      (node (ref "C18") (pin "1") (pinfunction "1_1") (pintype "passive"))
      (node (ref "C19") (pin "2") (pinfunction "2_2") (pintype "passive"))
      (node (ref "C2") (pin "2") (pinfunction "2_2") (pintype "passive"))
      (node (ref "C20") (pin "1") (pinfunction "1_1") (pintype "passive"))
      (node (ref "C21") (pin "2") (pinfunction "2_2") (pintype "passive"))
      (node (ref "C22") (pin "1") (pinfunction "1_1") (pintype "passive"))
      (node (ref "C23") (pin "2") (pinfunction "2_2") (pintype "passive"))
      (node (ref "C24") (pin "1") (pinfunction "1_1") (pintype "passive"))
      (node (ref "C25") (pin "2") (pinfunction "2_2") (pintype "passive"))
      (node (ref "C3") (pin "2") (pinfunction "2_2") (pintype "passive"))
      (node (ref "C4") (pin "2") (pinfunction "2_2") (pintype "passive"))
      (node (ref "C5") (pin "2") (pinfunction "2_2") (pintype "passive"))
      (node (ref "C6") (pin "2") (pinfunction "2_2") (pintype "passive"))
      (node (ref "C7") (pin "2") (pinfunction "2_2") (pintype "passive"))
      (node (ref "D1") (pin "2") (pinfunction "VSS_2") (pintype "passive"))
      (node (ref "D1") (pin "21") (pinfunction "VSS_21") (pintype "passive"))
      (node (ref "D1") (pin "24") (pinfunction "VSS_24") (pintype "passive"))
      (node (ref "D1") (pin "43") (pinfunction "VSS_43") (pintype "passive"))
      (node (ref "D1") (pin "46") (pinfunction "VSS_46") (pintype "passive"))
      (node (ref "D1") (pin "65") (pinfunction "VSS_65") (pintype "passive"))
      (node (ref "D1") (pin "89") (pinfunction "PAD_89") (pintype "passive"))
      (node (ref "D3") (pin "1") (pinfunction "A_1") (pintype "passive"))
      (node (ref "DD1") (pin "3") (pinfunction "GND_3") (pintype "passive"))
      (node (ref "R13") (pin "1") (pinfunction "1_1") (pintype "passive"))
      (node (ref "R4") (pin "1") (pinfunction "1_1") (pintype "passive"))
      (node (ref "R5") (pin "1") (pinfunction "1_1") (pintype "passive"))
      (node (ref "R8") (pin "1") (pinfunction "1_1") (pintype "passive"))
      (node (ref "R9") (pin "1") (pinfunction "1_1") (pintype "passive"))
      (node (ref "X1") (pin "4") (pinfunction "4_4") (pintype "passive"))
    )
    (net (code "88") (name "Net-(D2-K)") (class "Default")
      (node (ref "D2") (pin "2") (pinfunction "K_2") (pintype "passive"))
      (node (ref "R10") (pin "1") (pinfunction "1_1") (pintype "passive"))
    )
    (net (code "89") (name "Net-(D12-K)") (class "Default")
      (node (ref "D12") (pin "2") (pinfunction "K_2") (pintype "passive"))
      (node (ref "R60") (pin "1") (pinfunction "1_1") (pintype "passive"))
    )
    (net (code "90") (name "Net-(R1-Pad1)") (class "Default")
      (node (ref "R1") (pin "1") (pinfunction "1_1") (pintype "passive"))
      (node (ref "XS1") (pin "1") (pinfunction "1_1") (pintype "passive"))
    )
    (net (code "91") (name "Net-(R2-Pad1)") (class "Default")
      (node (ref "R2") (pin "1") (pinfunction "1_1") (pintype "passive"))
      (node (ref "XS2") (pin "1") (pinfunction "1_1") (pintype "passive"))
    )
    (net (code "92") (name "Net-(R4-Pad2)") (class "Default")
      (node (ref "R4") (pin "2") (pinfunction "2_2") (pintype "passive"))
      (node (ref "XS1") (pin "3") (pinfunction "3_3") (pintype "passive"))
    )
    (net (code "93") (name "Net-(R5-Pad2)") (class "Default")
      (node (ref "R5") (pin "2") (pinfunction "2_2") (pintype "passive"))
      (node (ref "XS2") (pin "3") (pinfunction "3_3") (pintype "passive"))
    )
    (net (code "94") (name "Net-(SW1-P2)") (class "Default")
      (node (ref "R7") (pin "1") (pinfunction "1_1") (pintype "passive"))
      (node (ref "SW1") (pin "1") (pinfunction "P2_1") (pintype "passive"))
    )
    (net (code "95") (name "Net-(SW1-P3)") (class "Default")
      (node (ref "R8") (pin "2") (pinfunction "2_2") (pintype "passive"))
      (node (ref "SW1") (pin "3") (pinfunction "P3_3") (pintype "passive"))
    )
    (net (code "96") (name "unconnected-(D1A-IOB23B-Pad34)") (class "Default")
      (node (ref "D1") (pin "34") (pinfunction "IOB23B_34") (pintype "passive+no_connect"))
    )
    (net (code "97") (name "unconnected-(D1A-IOB31B-Pad38)") (class "Default")
      (node (ref "D1") (pin "38") (pinfunction "IOB31B_38") (pintype "passive+no_connect"))
    )
    (net (code "98") (name "unconnected-(D1A-IOL22A-Pad13)") (class "Default")
      (node (ref "D1") (pin "13") (pinfunction "IOL22A_13") (pintype "passive+no_connect"))
    )
    (net (code "99") (name "unconnected-(DD1-CH1-Pad1)") (class "Default")
      (node (ref "DD1") (pin "1") (pinfunction "CH1_1") (pintype "passive+no_connect"))
    )
    (net (code "100") (name "unconnected-(DD1-CH3-Pad2)") (class "Default")
      (node (ref "DD1") (pin "2") (pinfunction "CH3_2") (pintype "passive+no_connect"))
    )
    (net (code "101") (name "unconnected-(DD1-CH4-Pad8)") (class "Default")
      (node (ref "DD1") (pin "8") (pinfunction "CH4_8") (pintype "passive+no_connect"))
    )
    (net (code "102") (name "unconnected-(DD1-CH5-Pad7)") (class "Default")
      (node (ref "DD1") (pin "7") (pinfunction "CH5_7") (pintype "passive+no_connect"))
    )
    (net (code "103") (name "unconnected-(DD1-CH6-Pad4)") (class "Default")
      (node (ref "DD1") (pin "4") (pinfunction "CH6_4") (pintype "passive+no_connect"))
    )
    (net (code "104") (name "unconnected-(DD1-CH8-Pad5)") (class "Default")
      (node (ref "DD1") (pin "5") (pinfunction "CH8_5") (pintype "passive+no_connect"))
    )
  )
)
